# Peripherals.net
KiCad netlist of a schematic drawn in Altium Designer
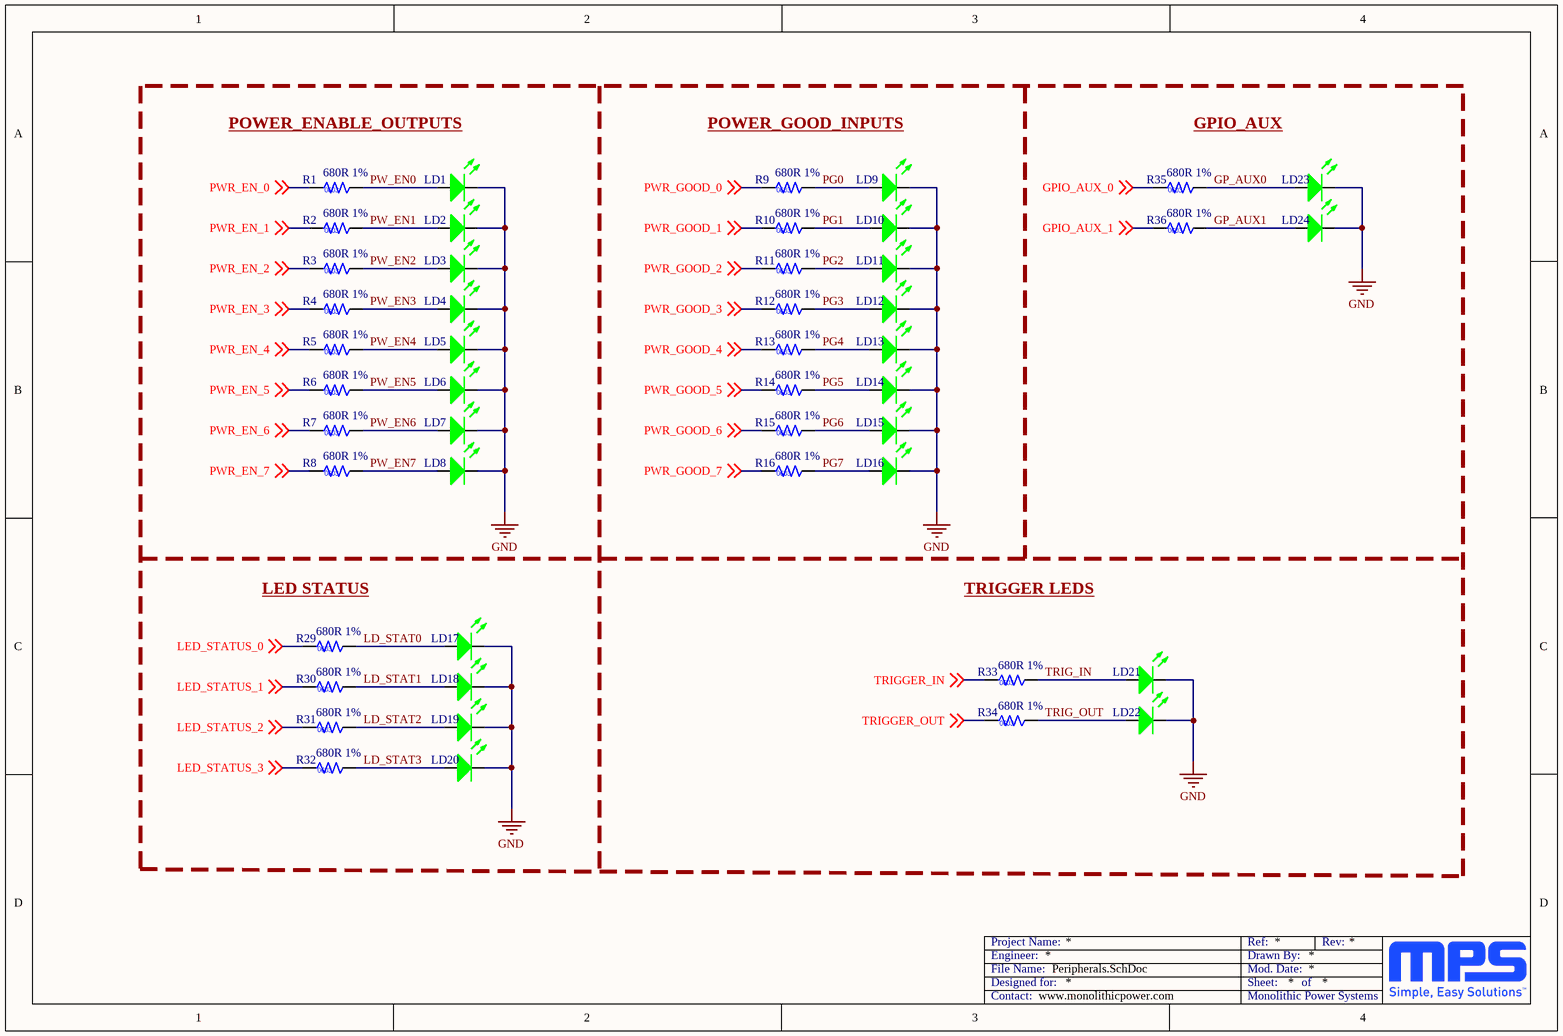
[diagram p0: Peripherals.SchDoc]

(export (version "E")
  (design (tool "Eeschema 10.0.6"))
  (components
    (comp (ref "LD1")
      (value "APHD1608LCGCK")
      (footprint "LED/0603/GREEN")
      (description "Green Light Emitting Diode")
      (fields (field (name "MANUFACTURER") "Kingbright"))
      (libsource (lib "DDR5_Nucleo_Shield_Symbols") (part "APHD1608LCGCK"))
    )
    (comp (ref "LD2")
      (value "APHD1608LCGCK")
      (footprint "LED/0603/GREEN")
      (description "Green Light Emitting Diode")
      (fields (field (name "MANUFACTURER") "Kingbright"))
      (libsource (lib "DDR5_Nucleo_Shield_Symbols") (part "APHD1608LCGCK"))
    )
    (comp (ref "LD3")
      (value "APHD1608LCGCK")
      (footprint "LED/0603/GREEN")
      (description "Green Light Emitting Diode")
      (fields (field (name "MANUFACTURER") "Kingbright"))
      (libsource (lib "DDR5_Nucleo_Shield_Symbols") (part "APHD1608LCGCK"))
    )
    (comp (ref "LD4")
      (value "APHD1608LCGCK")
      (footprint "LED/0603/GREEN")
      (description "Green Light Emitting Diode")
      (fields (field (name "MANUFACTURER") "Kingbright"))
      (libsource (lib "DDR5_Nucleo_Shield_Symbols") (part "APHD1608LCGCK"))
    )
    (comp (ref "LD5")
      (value "APHD1608LCGCK")
      (footprint "LED/0603/GREEN")
      (description "Green Light Emitting Diode")
      (fields (field (name "MANUFACTURER") "Kingbright"))
      (libsource (lib "DDR5_Nucleo_Shield_Symbols") (part "APHD1608LCGCK"))
    )
    (comp (ref "LD6")
      (value "APHD1608LCGCK")
      (footprint "LED/0603/GREEN")
      (description "Green Light Emitting Diode")
      (fields (field (name "MANUFACTURER") "Kingbright"))
      (libsource (lib "DDR5_Nucleo_Shield_Symbols") (part "APHD1608LCGCK"))
    )
    (comp (ref "LD7")
      (value "APHD1608LCGCK")
      (footprint "LED/0603/GREEN")
      (description "Green Light Emitting Diode")
      (fields (field (name "MANUFACTURER") "Kingbright"))
      (libsource (lib "DDR5_Nucleo_Shield_Symbols") (part "APHD1608LCGCK"))
    )
    (comp (ref "LD8")
      (value "APHD1608LCGCK")
      (footprint "LED/0603/GREEN")
      (description "Green Light Emitting Diode")
      (fields (field (name "MANUFACTURER") "Kingbright"))
      (libsource (lib "DDR5_Nucleo_Shield_Symbols") (part "APHD1608LCGCK"))
    )
    (comp (ref "LD9")
      (value "APHD1608LCGCK")
      (footprint "LED/0603/GREEN")
      (description "Green Light Emitting Diode")
      (fields (field (name "MANUFACTURER") "Kingbright"))
      (libsource (lib "DDR5_Nucleo_Shield_Symbols") (part "APHD1608LCGCK"))
    )
    (comp (ref "LD10")
      (value "APHD1608LCGCK")
      (footprint "LED/0603/GREEN")
      (description "Green Light Emitting Diode")
      (fields (field (name "MANUFACTURER") "Kingbright"))
      (libsource (lib "DDR5_Nucleo_Shield_Symbols") (part "APHD1608LCGCK"))
    )
    (comp (ref "LD11")
      (value "APHD1608LCGCK")
      (footprint "LED/0603/GREEN")
      (description "Green Light Emitting Diode")
      (fields (field (name "MANUFACTURER") "Kingbright"))
      (libsource (lib "DDR5_Nucleo_Shield_Symbols") (part "APHD1608LCGCK"))
    )
    (comp (ref "LD12")
      (value "APHD1608LCGCK")
      (footprint "LED/0603/GREEN")
      (description "Green Light Emitting Diode")
      (fields (field (name "MANUFACTURER") "Kingbright"))
      (libsource (lib "DDR5_Nucleo_Shield_Symbols") (part "APHD1608LCGCK"))
    )
    (comp (ref "LD13")
      (value "APHD1608LCGCK")
      (footprint "LED/0603/GREEN")
      (description "Green Light Emitting Diode")
      (fields (field (name "MANUFACTURER") "Kingbright"))
      (libsource (lib "DDR5_Nucleo_Shield_Symbols") (part "APHD1608LCGCK"))
    )
    (comp (ref "LD14")
      (value "APHD1608LCGCK")
      (footprint "LED/0603/GREEN")
      (description "Green Light Emitting Diode")
      (fields (field (name "MANUFACTURER") "Kingbright"))
      (libsource (lib "DDR5_Nucleo_Shield_Symbols") (part "APHD1608LCGCK"))
    )
    (comp (ref "LD15")
      (value "APHD1608LCGCK")
      (footprint "LED/0603/GREEN")
      (description "Green Light Emitting Diode")
      (fields (field (name "MANUFACTURER") "Kingbright"))
      (libsource (lib "DDR5_Nucleo_Shield_Symbols") (part "APHD1608LCGCK"))
    )
    (comp (ref "LD16")
      (value "APHD1608LCGCK")
      (footprint "LED/0603/GREEN")
      (description "Green Light Emitting Diode")
      (fields (field (name "MANUFACTURER") "Kingbright"))
      (libsource (lib "DDR5_Nucleo_Shield_Symbols") (part "APHD1608LCGCK"))
    )
    (comp (ref "LD17")
      (value "APHD1608LCGCK")
      (footprint "LED/0603/GREEN")
      (description "Green Light Emitting Diode")
      (fields (field (name "MANUFACTURER") "Kingbright"))
      (libsource (lib "DDR5_Nucleo_Shield_Symbols") (part "APHD1608LCGCK"))
    )
    (comp (ref "LD18")
      (value "APHD1608LCGCK")
      (footprint "LED/0603/GREEN")
      (description "Green Light Emitting Diode")
      (fields (field (name "MANUFACTURER") "Kingbright"))
      (libsource (lib "DDR5_Nucleo_Shield_Symbols") (part "APHD1608LCGCK"))
    )
    (comp (ref "LD19")
      (value "APHD1608LCGCK")
      (footprint "LED/0603/GREEN")
      (description "Green Light Emitting Diode")
      (fields (field (name "MANUFACTURER") "Kingbright"))
      (libsource (lib "DDR5_Nucleo_Shield_Symbols") (part "APHD1608LCGCK"))
    )
    (comp (ref "LD20")
      (value "APHD1608LCGCK")
      (footprint "LED/0603/GREEN")
      (description "Green Light Emitting Diode")
      (fields (field (name "MANUFACTURER") "Kingbright"))
      (libsource (lib "DDR5_Nucleo_Shield_Symbols") (part "APHD1608LCGCK"))
    )
    (comp (ref "LD21")
      (value "APHD1608LCGCK")
      (footprint "LED/0603/GREEN")
      (description "Green Light Emitting Diode")
      (fields (field (name "MANUFACTURER") "Kingbright"))
      (libsource (lib "DDR5_Nucleo_Shield_Symbols") (part "APHD1608LCGCK"))
    )
    (comp (ref "LD22")
      (value "APHD1608LCGCK")
      (footprint "LED/0603/GREEN")
      (description "Green Light Emitting Diode")
      (fields (field (name "MANUFACTURER") "Kingbright"))
      (libsource (lib "DDR5_Nucleo_Shield_Symbols") (part "APHD1608LCGCK"))
    )
    (comp (ref "LD23")
      (value "APHD1608LCGCK")
      (footprint "LED/0603/GREEN")
      (description "Green Light Emitting Diode")
      (fields (field (name "MANUFACTURER") "Kingbright"))
      (libsource (lib "DDR5_Nucleo_Shield_Symbols") (part "APHD1608LCGCK"))
    )
    (comp (ref "LD24")
      (value "APHD1608LCGCK")
      (footprint "LED/0603/GREEN")
      (description "Green Light Emitting Diode")
      (fields (field (name "MANUFACTURER") "Kingbright"))
      (libsource (lib "DDR5_Nucleo_Shield_Symbols") (part "APHD1608LCGCK"))
    )
    (comp (ref "R1")
      (value "680R 1%")
      (footprint "CC/NM 0603")
      (description "Resistores de película gruesa - SMD 680 ohm 1%")
      (fields
        (field (name "MANUFACTURER") "BOURNS")
        (field (name "MANUFACTURER PART NUMBER") "CR0603-FX-6800ELF")
      )
      (libsource (lib "DDR5_Nucleo_Shield_Symbols") (part "CR0603-FX-6800ELF"))
    )
    (comp (ref "R2")
      (value "680R 1%")
      (footprint "CC/NM 0603")
      (description "Resistores de película gruesa - SMD 680 ohm 1%")
      (fields
        (field (name "MANUFACTURER") "BOURNS")
        (field (name "MANUFACTURER PART NUMBER") "CR0603-FX-6800ELF")
      )
      (libsource (lib "DDR5_Nucleo_Shield_Symbols") (part "CR0603-FX-6800ELF"))
    )
    (comp (ref "R3")
      (value "680R 1%")
      (footprint "CC/NM 0603")
      (description "Resistores de película gruesa - SMD 680 ohm 1%")
      (fields
        (field (name "MANUFACTURER") "BOURNS")
        (field (name "MANUFACTURER PART NUMBER") "CR0603-FX-6800ELF")
      )
      (libsource (lib "DDR5_Nucleo_Shield_Symbols") (part "CR0603-FX-6800ELF"))
    )
    (comp (ref "R4")
      (value "680R 1%")
      (footprint "CC/NM 0603")
      (description "Resistores de película gruesa - SMD 680 ohm 1%")
      (fields
        (field (name "MANUFACTURER") "BOURNS")
        (field (name "MANUFACTURER PART NUMBER") "CR0603-FX-6800ELF")
      )
      (libsource (lib "DDR5_Nucleo_Shield_Symbols") (part "CR0603-FX-6800ELF"))
    )
    (comp (ref "R5")
      (value "680R 1%")
      (footprint "CC/NM 0603")
      (description "Resistores de película gruesa - SMD 680 ohm 1%")
      (fields
        (field (name "MANUFACTURER") "BOURNS")
        (field (name "MANUFACTURER PART NUMBER") "CR0603-FX-6800ELF")
      )
      (libsource (lib "DDR5_Nucleo_Shield_Symbols") (part "CR0603-FX-6800ELF"))
    )
    (comp (ref "R6")
      (value "680R 1%")
      (footprint "CC/NM 0603")
      (description "Resistores de película gruesa - SMD 680 ohm 1%")
      (fields
        (field (name "MANUFACTURER") "BOURNS")
        (field (name "MANUFACTURER PART NUMBER") "CR0603-FX-6800ELF")
      )
      (libsource (lib "DDR5_Nucleo_Shield_Symbols") (part "CR0603-FX-6800ELF"))
    )
    (comp (ref "R7")
      (value "680R 1%")
      (footprint "CC/NM 0603")
      (description "Resistores de película gruesa - SMD 680 ohm 1%")
      (fields
        (field (name "MANUFACTURER") "BOURNS")
        (field (name "MANUFACTURER PART NUMBER") "CR0603-FX-6800ELF")
      )
      (libsource (lib "DDR5_Nucleo_Shield_Symbols") (part "CR0603-FX-6800ELF"))
    )
    (comp (ref "R8")
      (value "680R 1%")
      (footprint "CC/NM 0603")
      (description "Resistores de película gruesa - SMD 680 ohm 1%")
      (fields
        (field (name "MANUFACTURER") "BOURNS")
        (field (name "MANUFACTURER PART NUMBER") "CR0603-FX-6800ELF")
      )
      (libsource (lib "DDR5_Nucleo_Shield_Symbols") (part "CR0603-FX-6800ELF"))
    )
    (comp (ref "R9")
      (value "680R 1%")
      (footprint "CC/NM 0603")
      (description "Resistores de película gruesa - SMD 680 ohm 1%")
      (fields
        (field (name "MANUFACTURER") "BOURNS")
        (field (name "MANUFACTURER PART NUMBER") "CR0603-FX-6800ELF")
      )
      (libsource (lib "DDR5_Nucleo_Shield_Symbols") (part "CR0603-FX-6800ELF"))
    )
    (comp (ref "R10")
      (value "680R 1%")
      (footprint "CC/NM 0603")
      (description "Resistores de película gruesa - SMD 680 ohm 1%")
      (fields
        (field (name "MANUFACTURER") "BOURNS")
        (field (name "MANUFACTURER PART NUMBER") "CR0603-FX-6800ELF")
      )
      (libsource (lib "DDR5_Nucleo_Shield_Symbols") (part "CR0603-FX-6800ELF"))
    )
    (comp (ref "R11")
      (value "680R 1%")
      (footprint "CC/NM 0603")
      (description "Resistores de película gruesa - SMD 680 ohm 1%")
      (fields
        (field (name "MANUFACTURER") "BOURNS")
        (field (name "MANUFACTURER PART NUMBER") "CR0603-FX-6800ELF")
      )
      (libsource (lib "DDR5_Nucleo_Shield_Symbols") (part "CR0603-FX-6800ELF"))
    )
    (comp (ref "R12")
      (value "680R 1%")
      (footprint "CC/NM 0603")
      (description "Resistores de película gruesa - SMD 680 ohm 1%")
      (fields
        (field (name "MANUFACTURER") "BOURNS")
        (field (name "MANUFACTURER PART NUMBER") "CR0603-FX-6800ELF")
      )
      (libsource (lib "DDR5_Nucleo_Shield_Symbols") (part "CR0603-FX-6800ELF"))
    )
    (comp (ref "R13")
      (value "680R 1%")
      (footprint "CC/NM 0603")
      (description "Resistores de película gruesa - SMD 680 ohm 1%")
      (fields
        (field (name "MANUFACTURER") "BOURNS")
        (field (name "MANUFACTURER PART NUMBER") "CR0603-FX-6800ELF")
      )
      (libsource (lib "DDR5_Nucleo_Shield_Symbols") (part "CR0603-FX-6800ELF"))
    )
    (comp (ref "R14")
      (value "680R 1%")
      (footprint "CC/NM 0603")
      (description "Resistores de película gruesa - SMD 680 ohm 1%")
      (fields
        (field (name "MANUFACTURER") "BOURNS")
        (field (name "MANUFACTURER PART NUMBER") "CR0603-FX-6800ELF")
      )
      (libsource (lib "DDR5_Nucleo_Shield_Symbols") (part "CR0603-FX-6800ELF"))
    )
    (comp (ref "R15")
      (value "680R 1%")
      (footprint "CC/NM 0603")
      (description "Resistores de película gruesa - SMD 680 ohm 1%")
      (fields
        (field (name "MANUFACTURER") "BOURNS")
        (field (name "MANUFACTURER PART NUMBER") "CR0603-FX-6800ELF")
      )
      (libsource (lib "DDR5_Nucleo_Shield_Symbols") (part "CR0603-FX-6800ELF"))
    )
    (comp (ref "R16")
      (value "680R 1%")
      (footprint "CC/NM 0603")
      (description "Resistores de película gruesa - SMD 680 ohm 1%")
      (fields
        (field (name "MANUFACTURER") "BOURNS")
        (field (name "MANUFACTURER PART NUMBER") "CR0603-FX-6800ELF")
      )
      (libsource (lib "DDR5_Nucleo_Shield_Symbols") (part "CR0603-FX-6800ELF"))
    )
    (comp (ref "R29")
      (value "680R 1%")
      (footprint "CC/NM 0603")
      (description "Resistores de película gruesa - SMD 680 ohm 1%")
      (fields
        (field (name "MANUFACTURER") "BOURNS")
        (field (name "MANUFACTURER PART NUMBER") "CR0603-FX-6800ELF")
      )
      (libsource (lib "DDR5_Nucleo_Shield_Symbols") (part "CR0603-FX-6800ELF"))
    )
    (comp (ref "R30")
      (value "680R 1%")
      (footprint "CC/NM 0603")
      (description "Resistores de película gruesa - SMD 680 ohm 1%")
      (fields
        (field (name "MANUFACTURER") "BOURNS")
        (field (name "MANUFACTURER PART NUMBER") "CR0603-FX-6800ELF")
      )
      (libsource (lib "DDR5_Nucleo_Shield_Symbols") (part "CR0603-FX-6800ELF"))
    )
    (comp (ref "R31")
      (value "680R 1%")
      (footprint "CC/NM 0603")
      (description "Resistores de película gruesa - SMD 680 ohm 1%")
      (fields
        (field (name "MANUFACTURER") "BOURNS")
        (field (name "MANUFACTURER PART NUMBER") "CR0603-FX-6800ELF")
      )
      (libsource (lib "DDR5_Nucleo_Shield_Symbols") (part "CR0603-FX-6800ELF"))
    )
    (comp (ref "R32")
      (value "680R 1%")
      (footprint "CC/NM 0603")
      (description "Resistores de película gruesa - SMD 680 ohm 1%")
      (fields
        (field (name "MANUFACTURER") "BOURNS")
        (field (name "MANUFACTURER PART NUMBER") "CR0603-FX-6800ELF")
      )
      (libsource (lib "DDR5_Nucleo_Shield_Symbols") (part "CR0603-FX-6800ELF"))
    )
    (comp (ref "R33")
      (value "680R 1%")
      (footprint "CC/NM 0603")
      (description "Resistores de película gruesa - SMD 680 ohm 1%")
      (fields
        (field (name "MANUFACTURER") "BOURNS")
        (field (name "MANUFACTURER PART NUMBER") "CR0603-FX-6800ELF")
      )
      (libsource (lib "DDR5_Nucleo_Shield_Symbols") (part "CR0603-FX-6800ELF"))
    )
    (comp (ref "R34")
      (value "680R 1%")
      (footprint "CC/NM 0603")
      (description "Resistores de película gruesa - SMD 680 ohm 1%")
      (fields
        (field (name "MANUFACTURER") "BOURNS")
        (field (name "MANUFACTURER PART NUMBER") "CR0603-FX-6800ELF")
      )
      (libsource (lib "DDR5_Nucleo_Shield_Symbols") (part "CR0603-FX-6800ELF"))
    )
    (comp (ref "R35")
      (value "680R 1%")
      (footprint "CC/NM 0603")
      (description "Resistores de película gruesa - SMD 680 ohm 1%")
      (fields
        (field (name "MANUFACTURER") "BOURNS")
        (field (name "MANUFACTURER PART NUMBER") "CR0603-FX-6800ELF")
      )
      (libsource (lib "DDR5_Nucleo_Shield_Symbols") (part "CR0603-FX-6800ELF"))
    )
    (comp (ref "R36")
      (value "680R 1%")
      (footprint "CC/NM 0603")
      (description "Resistores de película gruesa - SMD 680 ohm 1%")
      (fields
        (field (name "MANUFACTURER") "BOURNS")
        (field (name "MANUFACTURER PART NUMBER") "CR0603-FX-6800ELF")
      )
      (libsource (lib "DDR5_Nucleo_Shield_Symbols") (part "CR0603-FX-6800ELF"))
    )
  )
  (nets
    (net (code "1") (name "/GP_AUX0") (class "Default")
      (node (ref "LD23") (pin "1") (pinfunction "A_1") (pintype "passive"))
      (node (ref "R35") (pin "2") (pinfunction "2_2") (pintype "passive"))
    )
    (net (code "2") (name "/GP_AUX1") (class "Default")
      (node (ref "LD24") (pin "1") (pinfunction "A_1") (pintype "passive"))
      (node (ref "R36") (pin "2") (pinfunction "2_2") (pintype "passive"))
    )
    (net (code "3") (name "/LD_STAT0") (class "Default")
      (node (ref "LD17") (pin "1") (pinfunction "A_1") (pintype "passive"))
      (node (ref "R29") (pin "2") (pinfunction "2_2") (pintype "passive"))
    )
    (net (code "4") (name "/LD_STAT1") (class "Default")
      (node (ref "LD18") (pin "1") (pinfunction "A_1") (pintype "passive"))
      (node (ref "R30") (pin "2") (pinfunction "2_2") (pintype "passive"))
    )
    (net (code "5") (name "/LD_STAT2") (class "Default")
      (node (ref "LD19") (pin "1") (pinfunction "A_1") (pintype "passive"))
      (node (ref "R31") (pin "2") (pinfunction "2_2") (pintype "passive"))
    )
    (net (code "6") (name "/LD_STAT3") (class "Default")
      (node (ref "LD20") (pin "1") (pinfunction "A_1") (pintype "passive"))
      (node (ref "R32") (pin "2") (pinfunction "2_2") (pintype "passive"))
    )
    (net (code "7") (name "/PG0") (class "Default")
      (node (ref "LD9") (pin "1") (pinfunction "A_1") (pintype "passive"))
      (node (ref "R9") (pin "2") (pinfunction "2_2") (pintype "passive"))
    )
    (net (code "8") (name "/PG1") (class "Default")
      (node (ref "LD10") (pin "1") (pinfunction "A_1") (pintype "passive"))
      (node (ref "R10") (pin "2") (pinfunction "2_2") (pintype "passive"))
    )
    (net (code "9") (name "/PG2") (class "Default")
      (node (ref "LD11") (pin "1") (pinfunction "A_1") (pintype "passive"))
      (node (ref "R11") (pin "2") (pinfunction "2_2") (pintype "passive"))
    )
    (net (code "10") (name "/PG3") (class "Default")
      (node (ref "LD12") (pin "1") (pinfunction "A_1") (pintype "passive"))
      (node (ref "R12") (pin "2") (pinfunction "2_2") (pintype "passive"))
    )
    (net (code "11") (name "/PG4") (class "Default")
      (node (ref "LD13") (pin "1") (pinfunction "A_1") (pintype "passive"))
      (node (ref "R13") (pin "2") (pinfunction "2_2") (pintype "passive"))
    )
    (net (code "12") (name "/PG5") (class "Default")
      (node (ref "LD14") (pin "1") (pinfunction "A_1") (pintype "passive"))
      (node (ref "R14") (pin "2") (pinfunction "2_2") (pintype "passive"))
    )
    (net (code "13") (name "/PG6") (class "Default")
      (node (ref "LD15") (pin "1") (pinfunction "A_1") (pintype "passive"))
      (node (ref "R15") (pin "2") (pinfunction "2_2") (pintype "passive"))
    )
    (net (code "14") (name "/PG7") (class "Default")
      (node (ref "LD16") (pin "1") (pinfunction "A_1") (pintype "passive"))
      (node (ref "R16") (pin "2") (pinfunction "2_2") (pintype "passive"))
    )
    (net (code "15") (name "/PW_EN0") (class "Default")
      (node (ref "LD1") (pin "1") (pinfunction "A_1") (pintype "passive"))
      (node (ref "R1") (pin "2") (pinfunction "2_2") (pintype "passive"))
    )
    (net (code "16") (name "/PW_EN1") (class "Default")
      (node (ref "LD2") (pin "1") (pinfunction "A_1") (pintype "passive"))
      (node (ref "R2") (pin "2") (pinfunction "2_2") (pintype "passive"))
    )
    (net (code "17") (name "/PW_EN2") (class "Default")
      (node (ref "LD3") (pin "1") (pinfunction "A_1") (pintype "passive"))
      (node (ref "R3") (pin "2") (pinfunction "2_2") (pintype "passive"))
    )
    (net (code "18") (name "/PW_EN3") (class "Default")
      (node (ref "LD4") (pin "1") (pinfunction "A_1") (pintype "passive"))
      (node (ref "R4") (pin "2") (pinfunction "2_2") (pintype "passive"))
    )
    (net (code "19") (name "/PW_EN4") (class "Default")
      (node (ref "LD5") (pin "1") (pinfunction "A_1") (pintype "passive"))
      (node (ref "R5") (pin "2") (pinfunction "2_2") (pintype "passive"))
    )
    (net (code "20") (name "/PW_EN5") (class "Default")
      (node (ref "LD6") (pin "1") (pinfunction "A_1") (pintype "passive"))
      (node (ref "R6") (pin "2") (pinfunction "2_2") (pintype "passive"))
    )
    (net (code "21") (name "/PW_EN6") (class "Default")
      (node (ref "LD7") (pin "1") (pinfunction "A_1") (pintype "passive"))
      (node (ref "R7") (pin "2") (pinfunction "2_2") (pintype "passive"))
    )
    (net (code "22") (name "/PW_EN7") (class "Default")
      (node (ref "LD8") (pin "1") (pinfunction "A_1") (pintype "passive"))
      (node (ref "R8") (pin "2") (pinfunction "2_2") (pintype "passive"))
    )
    (net (code "23") (name "/TRIG_IN") (class "Default")
      (node (ref "LD21") (pin "1") (pinfunction "A_1") (pintype "passive"))
      (node (ref "R33") (pin "2") (pinfunction "2_2") (pintype "passive"))
    )
    (net (code "24") (name "/TRIG_OUT") (class "Default")
      (node (ref "LD22") (pin "1") (pinfunction "A_1") (pintype "passive"))
      (node (ref "R34") (pin "2") (pinfunction "2_2") (pintype "passive"))
    )
    (net (code "25") (name "GND") (class "Default")
      (node (ref "LD1") (pin "2") (pinfunction "K_2") (pintype "passive"))
      (node (ref "LD10") (pin "2") (pinfunction "K_2") (pintype "passive"))
      (node (ref "LD11") (pin "2") (pinfunction "K_2") (pintype "passive"))
      (node (ref "LD12") (pin "2") (pinfunction "K_2") (pintype "passive"))
      (node (ref "LD13") (pin "2") (pinfunction "K_2") (pintype "passive"))
      (node (ref "LD14") (pin "2") (pinfunction "K_2") (pintype "passive"))
      (node (ref "LD15") (pin "2") (pinfunction "K_2") (pintype "passive"))
      (node (ref "LD16") (pin "2") (pinfunction "K_2") (pintype "passive"))
      (node (ref "LD17") (pin "2") (pinfunction "K_2") (pintype "passive"))
      (node (ref "LD18") (pin "2") (pinfunction "K_2") (pintype "passive"))
      (node (ref "LD19") (pin "2") (pinfunction "K_2") (pintype "passive"))
      (node (ref "LD2") (pin "2") (pinfunction "K_2") (pintype "passive"))
      (node (ref "LD20") (pin "2") (pinfunction "K_2") (pintype "passive"))
      (node (ref "LD21") (pin "2") (pinfunction "K_2") (pintype "passive"))
      (node (ref "LD22") (pin "2") (pinfunction "K_2") (pintype "passive"))
      (node (ref "LD23") (pin "2") (pinfunction "K_2") (pintype "passive"))
      (node (ref "LD24") (pin "2") (pinfunction "K_2") (pintype "passive"))
      (node (ref "LD3") (pin "2") (pinfunction "K_2") (pintype "passive"))
      (node (ref "LD4") (pin "2") (pinfunction "K_2") (pintype "passive"))
      (node (ref "LD5") (pin "2") (pinfunction "K_2") (pintype "passive"))
      (node (ref "LD6") (pin "2") (pinfunction "K_2") (pintype "passive"))
      (node (ref "LD7") (pin "2") (pinfunction "K_2") (pintype "passive"))
      (node (ref "LD8") (pin "2") (pinfunction "K_2") (pintype "passive"))
      (node (ref "LD9") (pin "2") (pinfunction "K_2") (pintype "passive"))
    )
    (net (code "26") (name "GPIO_AUX_0") (class "Default")
      (node (ref "R35") (pin "1") (pinfunction "1_1") (pintype "passive"))
    )
    (net (code "27") (name "GPIO_AUX_1") (class "Default")
      (node (ref "R36") (pin "1") (pinfunction "1_1") (pintype "passive"))
    )
    (net (code "28") (name "LED_STATUS_0") (class "Default")
      (node (ref "R29") (pin "1") (pinfunction "1_1") (pintype "passive"))
    )
    (net (code "29") (name "LED_STATUS_1") (class "Default")
      (node (ref "R30") (pin "1") (pinfunction "1_1") (pintype "passive"))
    )
    (net (code "30") (name "LED_STATUS_2") (class "Default")
      (node (ref "R31") (pin "1") (pinfunction "1_1") (pintype "passive"))
    )
    (net (code "31") (name "LED_STATUS_3") (class "Default")
      (node (ref "R32") (pin "1") (pinfunction "1_1") (pintype "passive"))
    )
    (net (code "32") (name "PWR_EN_0") (class "Default")
      (node (ref "R1") (pin "1") (pinfunction "1_1") (pintype "passive"))
    )
    (net (code "33") (name "PWR_EN_1") (class "Default")
      (node (ref "R2") (pin "1") (pinfunction "1_1") (pintype "passive"))
    )
    (net (code "34") (name "PWR_EN_2") (class "Default")
      (node (ref "R3") (pin "1") (pinfunction "1_1") (pintype "passive"))
    )
    (net (code "35") (name "PWR_EN_3") (class "Default")
      (node (ref "R4") (pin "1") (pinfunction "1_1") (pintype "passive"))
    )
    (net (code "36") (name "PWR_EN_4") (class "Default")
      (node (ref "R5") (pin "1") (pinfunction "1_1") (pintype "passive"))
    )
    (net (code "37") (name "PWR_EN_5") (class "Default")
      (node (ref "R6") (pin "1") (pinfunction "1_1") (pintype "passive"))
    )
    (net (code "38") (name "PWR_EN_6") (class "Default")
      (node (ref "R7") (pin "1") (pinfunction "1_1") (pintype "passive"))
    )
    (net (code "39") (name "PWR_EN_7") (class "Default")
      (node (ref "R8") (pin "1") (pinfunction "1_1") (pintype "passive"))
    )
    (net (code "40") (name "PWR_GOOD_0") (class "Default")
      (node (ref "R9") (pin "1") (pinfunction "1_1") (pintype "passive"))
    )
    (net (code "41") (name "PWR_GOOD_1") (class "Default")
      (node (ref "R10") (pin "1") (pinfunction "1_1") (pintype "passive"))
    )
    (net (code "42") (name "PWR_GOOD_2") (class "Default")
      (node (ref "R11") (pin "1") (pinfunction "1_1") (pintype "passive"))
    )
    (net (code "43") (name "PWR_GOOD_3") (class "Default")
      (node (ref "R12") (pin "1") (pinfunction "1_1") (pintype "passive"))
    )
    (net (code "44") (name "PWR_GOOD_4") (class "Default")
      (node (ref "R13") (pin "1") (pinfunction "1_1") (pintype "passive"))
    )
    (net (code "45") (name "PWR_GOOD_5") (class "Default")
      (node (ref "R14") (pin "1") (pinfunction "1_1") (pintype "passive"))
    )
    (net (code "46") (name "PWR_GOOD_6") (class "Default")
      (node (ref "R15") (pin "1") (pinfunction "1_1") (pintype "passive"))
    )
    (net (code "47") (name "PWR_GOOD_7") (class "Default")
      (node (ref "R16") (pin "1") (pinfunction "1_1") (pintype "passive"))
    )
    (net (code "48") (name "TRIGGER_IN") (class "Default")
      (node (ref "R33") (pin "1") (pinfunction "1_1") (pintype "passive"))
    )
    (net (code "49") (name "TRIGGER_OUT") (class "Default")
      (node (ref "R34") (pin "1") (pinfunction "1_1") (pintype "passive"))
    )
  )
)
